# PWR_Det.net
KiCad netlist of a schematic drawn in Altium Designer
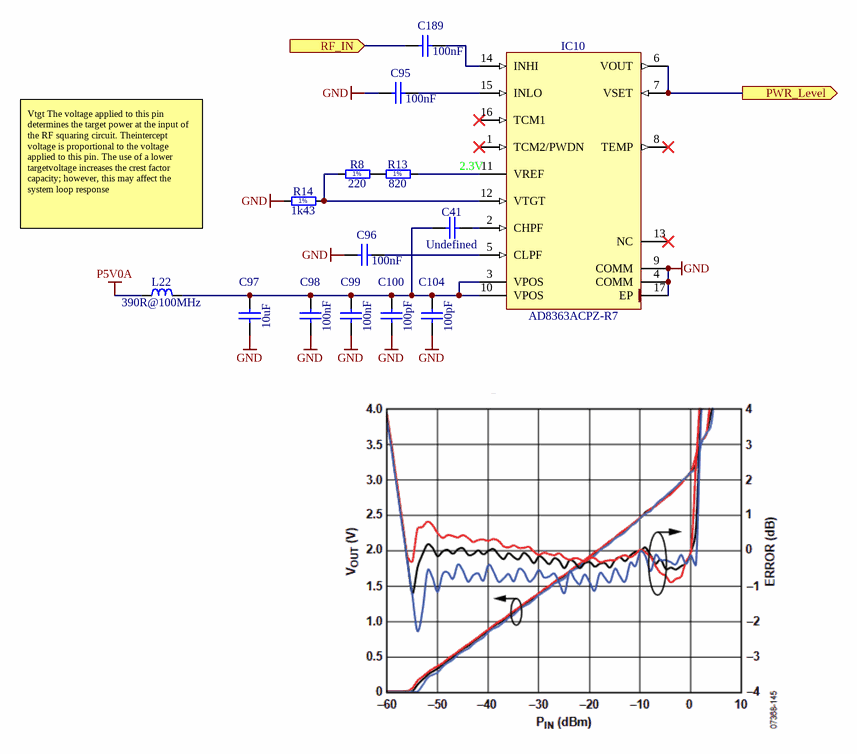
[diagram p0: PWR_Det.SchDoc]

(export (version "E")
  (design (tool "Eeschema 10.0.6"))
  (components
    (comp (ref "C41")
      (value "Undefined")
      (footprint "CAPC1608X90N")
      (description "Non-polarised capacitor")
      (fields (field (name "PART NUMBER") "CC0603_NO-VALUE") (field (name "AUTHOR") "CERN DEM MR"))
      (libsource (lib "Capacitors") (part "Capacitor - non polarized"))
    )
    (comp (ref "C95")
      (value "100nF")
      (footprint "CAPC1005X55N")
      (description "Non-polarised capacitor")
      (fields
        (field (name "PART NUMBER") "CC0402_100NF_16V_10%_X5R")
        (field (name "VOLTAGE") "16V")
        (field (name "AUTHOR") "CERN DEM JLC")
      )
      (libsource (lib "Capacitors") (part "Capacitor - non polarized"))
    )
    (comp (ref "C96")
      (value "100nF")
      (footprint "CAPC1005X55N")
      (description "Non-polarised capacitor")
      (fields
        (field (name "PART NUMBER") "CC0402_100NF_16V_10%_X7R")
        (field (name "VOLTAGE") "16V")
        (field (name "AUTHOR") "CERN DEM JLC")
      )
      (libsource (lib "Capacitors") (part "Capacitor - non polarized"))
    )
    (comp (ref "C97")
      (value "10uF")
      (footprint "CAPC1608X80N")
      (description "Non-polarised capacitor")
      (fields
        (field (name "PART NUMBER") "CC0603_10UF_16V_20%_X5R")
        (field (name "VOLTAGE") "16V")
        (field (name "AUTHOR") "CERN DEM MR")
      )
      (libsource (lib "Capacitors") (part "Capacitor - non polarized"))
    )
    (comp (ref "C98")
      (value "100nF")
      (footprint "CAPC1005X55N")
      (description "Non-polarised capacitor")
      (fields
        (field (name "PART NUMBER") "CC0402_100NF_16V_10%_X7R")
        (field (name "VOLTAGE") "16V")
        (field (name "AUTHOR") "CERN DEM JLC")
      )
      (libsource (lib "Capacitors") (part "Capacitor - non polarized"))
    )
    (comp (ref "C99")
      (value "100nF")
      (footprint "CAPC1005X55N")
      (description "Non-polarised capacitor")
      (fields
        (field (name "PART NUMBER") "CC0402_100NF_16V_10%_X7R")
        (field (name "VOLTAGE") "16V")
        (field (name "AUTHOR") "CERN DEM JLC")
      )
      (libsource (lib "Capacitors") (part "Capacitor - non polarized"))
    )
    (comp (ref "C100")
      (value "100pF")
      (footprint "CAPC1005X55N")
      (description "Non-polarised capacitor")
      (fields
        (field (name "PART NUMBER") "CC0402_100PF_50V_5%_C0G")
        (field (name "VOLTAGE") "50V")
        (field (name "AUTHOR") "CERN DEM JLC")
      )
      (libsource (lib "Capacitors") (part "Capacitor - non polarized"))
    )
    (comp (ref "C104")
      (value "100pF")
      (footprint "CAPC1005X55N")
      (description "Non-polarised capacitor")
      (fields
        (field (name "PART NUMBER") "CC0402_100PF_50V_5%_C0G")
        (field (name "VOLTAGE") "50V")
        (field (name "AUTHOR") "CERN DEM JLC")
      )
      (libsource (lib "Capacitors") (part "Capacitor - non polarized"))
    )
    (comp (ref "C189")
      (value "100nF")
      (footprint "CAPC1005X55N")
      (description "Non-polarised capacitor")
      (fields
        (field (name "PART NUMBER") "CC0402_100NF_16V_10%_X5R")
        (field (name "VOLTAGE") "16V")
        (field (name "AUTHOR") "CERN DEM JLC")
      )
      (libsource (lib "Capacitors") (part "Capacitor - non polarized"))
    )
    (comp (ref "IC10")
      (value "AD8363ACPZ-R7")
      (footprint "QFN65P400X400X80-17N-S240")
      (description "50Hz to 6GHz, 50 dB TruPwr Detector")
      (fields (field (name "MANUFACTURER") "ANALOG DEVICES") (field (name "AUTHOR") "CERN DEM JLC"))
      (libsource (lib "ICs And Semiconductors") (part "AD8363"))
    )
    (comp (ref "L22")
      (value "390R@100MHz")
      (footprint "INDC1608X95N")
      (description "Inductor")
      (fields
        (field (name "PART NUMBER") "IND0603_TDK_MPZ1608R391A")
        (field (name "POWER") "1.2A")
        (field (name "AUTHOR") "CERN DEM JLC")
      )
      (libsource (lib "Inductors & Transformers") (part "Inductor"))
    )
    (comp (ref "R8")
      (value "220")
      (footprint "RESC1005X40N")
      (description "Resistor - 1%")
      (fields
        (field (name "PART NUMBER") "R0402_220R_1%_0.0625W_100PPM")
        (field (name "POWER") "0.0625W")
        (field (name "AUTHOR") "CERN DEM JLC")
      )
      (libsource (lib "Resistors") (part "Resistor - 1%"))
    )
    (comp (ref "R13")
      (value "820")
      (footprint "RESC1005X40N")
      (description "Resistor - 1%")
      (fields
        (field (name "PART NUMBER") "R0402_820R_1%_0.0625W_100PPM")
        (field (name "POWER") "0.0625W")
        (field (name "AUTHOR") "CERN DEM JLC")
      )
      (libsource (lib "Resistors") (part "Resistor - 1%"))
    )
    (comp (ref "R14")
      (value "1k43")
      (footprint "RESC1005X40N")
      (description "Resistor - 1%")
      (fields
        (field (name "PART NUMBER") "R0402_1K43_1%_0.0625W_100PPM")
        (field (name "POWER") "0.0625W")
        (field (name "AUTHOR") "CERN DEM JLC")
      )
      (libsource (lib "Resistors") (part "Resistor - 1%"))
    )
  )
  (nets
    (net (code "1") (name "/PWR_Level") (class "Default")
      (node (ref "IC10") (pin "6") (pinfunction "VOUT_6") (pintype "output"))
      (node (ref "IC10") (pin "7") (pinfunction "VSET_7") (pintype "input"))
    )
    (net (code "2") (name "/RF_IN") (class "Default")
      (node (ref "C189") (pin "2") (pinfunction "2_2") (pintype "passive"))
    )
    (net (code "3") (name "GND") (class "Default")
      (node (ref "C100") (pin "1") (pinfunction "1_1") (pintype "passive"))
      (node (ref "C104") (pin "1") (pinfunction "1_1") (pintype "passive"))
      (node (ref "C95") (pin "2") (pinfunction "2_2") (pintype "passive"))
      (node (ref "C96") (pin "1") (pinfunction "1_1") (pintype "passive"))
      (node (ref "C97") (pin "1") (pinfunction "1_1") (pintype "passive"))
      (node (ref "C98") (pin "1") (pinfunction "1_1") (pintype "passive"))
      (node (ref "C99") (pin "1") (pinfunction "1_1") (pintype "passive"))
      (node (ref "IC10") (pin "17") (pinfunction "EP_17") (pintype "power_in"))
      (node (ref "IC10") (pin "4") (pinfunction "COMM_4") (pintype "power_in"))
      (node (ref "IC10") (pin "9") (pinfunction "COMM_9") (pintype "power_in"))
      (node (ref "R14") (pin "1") (pinfunction "1_1") (pintype "passive"))
    )
    (net (code "4") (name "Net-(C100-Pad2)") (class "Default")
      (node (ref "C100") (pin "2") (pinfunction "2_2") (pintype "passive"))
      (node (ref "C104") (pin "2") (pinfunction "2_2") (pintype "passive"))
      (node (ref "C41") (pin "1") (pinfunction "1_1") (pintype "passive"))
      (node (ref "C97") (pin "2") (pinfunction "2_2") (pintype "passive"))
      (node (ref "C98") (pin "2") (pinfunction "2_2") (pintype "passive"))
      (node (ref "C99") (pin "2") (pinfunction "2_2") (pintype "passive"))
      (node (ref "IC10") (pin "10") (pinfunction "VPOS_10") (pintype "power_in"))
      (node (ref "IC10") (pin "3") (pinfunction "VPOS_3") (pintype "power_in"))
      (node (ref "L22") (pin "2") (pinfunction "2_2") (pintype "passive"))
    )
    (net (code "5") (name "Net-(IC10-CHPF)") (class "Default")
      (node (ref "C41") (pin "2") (pinfunction "2_2") (pintype "passive"))
      (node (ref "IC10") (pin "2") (pinfunction "CHPF_2") (pintype "input"))
    )
    (net (code "6") (name "Net-(IC10-CLPF)") (class "Default")
      (node (ref "C96") (pin "2") (pinfunction "2_2") (pintype "passive"))
      (node (ref "IC10") (pin "5") (pinfunction "CLPF_5") (pintype "input"))
    )
    (net (code "7") (name "Net-(IC10-INHI)") (class "Default")
      (node (ref "C189") (pin "1") (pinfunction "1_1") (pintype "passive"))
      (node (ref "IC10") (pin "14") (pinfunction "INHI_14") (pintype "input"))
    )
    (net (code "8") (name "Net-(IC10-INLO)") (class "Default")
      (node (ref "C95") (pin "1") (pinfunction "1_1") (pintype "passive"))
      (node (ref "IC10") (pin "15") (pinfunction "INLO_15") (pintype "input"))
    )
    (net (code "9") (name "Net-(IC10-VREF)") (class "Default")
      (node (ref "IC10") (pin "11") (pinfunction "VREF_11") (pintype "power_in"))
      (node (ref "R13") (pin "2") (pinfunction "2_2") (pintype "passive"))
    )
    (net (code "10") (name "Net-(IC10-VTGT)") (class "Default")
      (node (ref "IC10") (pin "12") (pinfunction "VTGT_12") (pintype "input"))
      (node (ref "R14") (pin "2") (pinfunction "2_2") (pintype "passive"))
      (node (ref "R8") (pin "1") (pinfunction "1_1") (pintype "passive"))
    )
    (net (code "11") (name "Net-(R13-Pad1)") (class "Default")
      (node (ref "R13") (pin "1") (pinfunction "1_1") (pintype "passive"))
      (node (ref "R8") (pin "2") (pinfunction "2_2") (pintype "passive"))
    )
    (net (code "12") (name "P5V0A") (class "Default")
      (node (ref "L22") (pin "1") (pinfunction "1_1") (pintype "passive"))
    )
    (net (code "13") (name "unconnected-(IC10-NC-Pad13)") (class "Default")
      (node (ref "IC10") (pin "13") (pinfunction "NC_13") (pintype "passive+no_connect"))
    )
    (net (code "14") (name "unconnected-(IC10-TCM1-Pad16)") (class "Default")
      (node (ref "IC10") (pin "16") (pinfunction "TCM1_16") (pintype "input+no_connect"))
    )
    (net (code "15") (name "unconnected-(IC10-TCM2{slash}PWDN-Pad1)") (class "Default")
      (node (ref "IC10") (pin "1") (pinfunction "TCM2/PWDN_1") (pintype "input+no_connect"))
    )
    (net (code "16") (name "unconnected-(IC10-TEMP-Pad8)") (class "Default")
      (node (ref "IC10") (pin "8") (pinfunction "TEMP_8") (pintype "output+no_connect"))
    )
  )
)
